# scheme.net
KiCad netlist of a schematic drawn in EAGLE
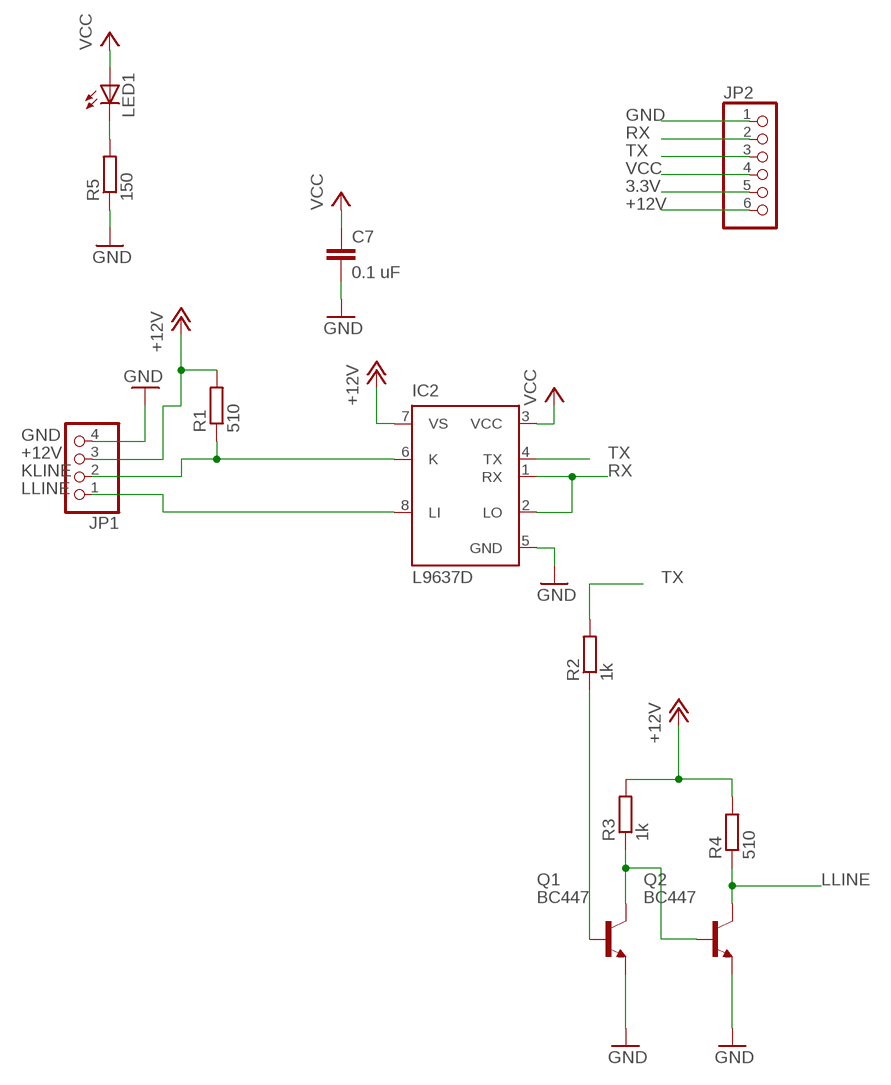
[diagram p0: schematic, sheet 1]

(export (version "E")
  (design (tool "Eeschema 10.0.6"))
  (components
    (comp (ref "C7")
      (value "0.1 uF")
      (footprint "eagle-import:C0805K")
      (libsource (lib "eagle-import") (part "C-EUC0805K"))
    )
    (comp (ref "IC2")
      (value "L9637D")
      (footprint "eagle-import:SO08")
      (libsource (lib "eagle-import") (part "L9637D"))
    )
    (comp (ref "JP1")
      (value "PINHD-1X4")
      (footprint "eagle-import:1X04")
      (libsource (lib "eagle-import") (part "PINHD-1X4"))
    )
    (comp (ref "JP2")
      (value "PINHD-1X6")
      (footprint "eagle-import:1X06")
      (libsource (lib "eagle-import") (part "PINHD-1X6"))
    )
    (comp (ref "LED1")
      (value "LEDSML1206")
      (footprint "eagle-import:SML1206")
      (libsource (lib "eagle-import") (part "LEDSML1206"))
    )
    (comp (ref "Q1")
      (value "BC447")
      (footprint "eagle-import:TO92-EBC")
      (libsource (lib "eagle-import") (part "BC447"))
    )
    (comp (ref "Q2")
      (value "BC447")
      (footprint "eagle-import:TO92-EBC")
      (libsource (lib "eagle-import") (part "BC447"))
    )
    (comp (ref "R1")
      (value "510")
      (footprint "eagle-import:R0805")
      (libsource (lib "eagle-import") (part "R-EU_R0805"))
    )
    (comp (ref "R2")
      (value "1k")
      (footprint "eagle-import:R0805")
      (libsource (lib "eagle-import") (part "R-EU_R0805"))
    )
    (comp (ref "R3")
      (value "1k")
      (footprint "eagle-import:R0805")
      (libsource (lib "eagle-import") (part "R-EU_R0805"))
    )
    (comp (ref "R4")
      (value "510")
      (footprint "eagle-import:R0805")
      (libsource (lib "eagle-import") (part "R-EU_R0805"))
    )
    (comp (ref "R5")
      (value "150")
      (footprint "eagle-import:R0805")
      (libsource (lib "eagle-import") (part "R-EU_R0805"))
    )
  )
  (nets
    (net (code "1") (name "+12V") (class "Default")
      (node (ref "IC2") (pin "7") (pinfunction "VS_7") (pintype "power_in"))
      (node (ref "JP1") (pin "3") (pinfunction "3_3") (pintype "passive"))
      (node (ref "JP2") (pin "6") (pinfunction "6_6") (pintype "passive"))
      (node (ref "R1") (pin "2") (pinfunction "2_2") (pintype "passive"))
      (node (ref "R3") (pin "2") (pinfunction "2_2") (pintype "passive"))
      (node (ref "R4") (pin "2") (pinfunction "2_2") (pintype "passive"))
    )
    (net (code "2") (name "/3.3V") (class "Default")
      (node (ref "JP2") (pin "5") (pinfunction "5_5") (pintype "passive"))
    )
    (net (code "3") (name "/KLINE") (class "Default")
      (node (ref "IC2") (pin "6") (pinfunction "K_6") (pintype "input"))
      (node (ref "JP1") (pin "2") (pinfunction "2_2") (pintype "passive"))
      (node (ref "R1") (pin "1") (pinfunction "1_1") (pintype "passive"))
    )
    (net (code "4") (name "/LLINE") (class "Default")
      (node (ref "IC2") (pin "8") (pinfunction "LI_8") (pintype "input"))
      (node (ref "JP1") (pin "1") (pinfunction "1_1") (pintype "passive"))
      (node (ref "Q2") (pin "C") (pinfunction "C_C") (pintype "passive"))
      (node (ref "R4") (pin "1") (pinfunction "1_1") (pintype "passive"))
    )
    (net (code "5") (name "/RX") (class "Default")
      (node (ref "IC2") (pin "1") (pinfunction "RX_1") (pintype "output"))
      (node (ref "IC2") (pin "2") (pinfunction "LO_2") (pintype "output"))
      (node (ref "JP2") (pin "2") (pinfunction "2_2") (pintype "passive"))
    )
    (net (code "6") (name "/TX") (class "Default")
      (node (ref "IC2") (pin "4") (pinfunction "TX_4") (pintype "input"))
      (node (ref "JP2") (pin "3") (pinfunction "3_3") (pintype "passive"))
      (node (ref "R2") (pin "2") (pinfunction "2_2") (pintype "passive"))
    )
    (net (code "7") (name "GND") (class "Default")
      (node (ref "C7") (pin "2") (pinfunction "2_2") (pintype "passive"))
      (node (ref "IC2") (pin "5") (pinfunction "GND_5") (pintype "power_in"))
      (node (ref "JP1") (pin "4") (pinfunction "4_4") (pintype "passive"))
      (node (ref "JP2") (pin "1") (pinfunction "1_1") (pintype "passive"))
      (node (ref "Q1") (pin "E") (pinfunction "E_E") (pintype "passive"))
      (node (ref "Q2") (pin "E") (pinfunction "E_E") (pintype "passive"))
      (node (ref "R5") (pin "1") (pinfunction "1_1") (pintype "passive"))
    )
    (net (code "8") (name "Net-(LED1-PadC)") (class "Default")
      (node (ref "LED1") (pin "C") (pinfunction "C_C") (pintype "passive"))
      (node (ref "R5") (pin "2") (pinfunction "2_2") (pintype "passive"))
    )
    (net (code "9") (name "Net-(Q1-PadB)") (class "Default")
      (node (ref "Q1") (pin "B") (pinfunction "B_B") (pintype "passive"))
      (node (ref "R2") (pin "1") (pinfunction "1_1") (pintype "passive"))
    )
    (net (code "10") (name "Net-(Q1-PadC)") (class "Default")
      (node (ref "Q1") (pin "C") (pinfunction "C_C") (pintype "passive"))
      (node (ref "Q2") (pin "B") (pinfunction "B_B") (pintype "passive"))
      (node (ref "R3") (pin "1") (pinfunction "1_1") (pintype "passive"))
    )
    (net (code "11") (name "VCC") (class "Default")
      (node (ref "C7") (pin "1") (pinfunction "1_1") (pintype "passive"))
      (node (ref "IC2") (pin "3") (pinfunction "VCC_3") (pintype "power_in"))
      (node (ref "JP2") (pin "4") (pinfunction "4_4") (pintype "passive"))
      (node (ref "LED1") (pin "A") (pinfunction "A_A") (pintype "passive"))
    )
  )
)
